# CouchProtato-BOTTOM.net
KiCad netlist of a schematic drawn in EAGLE
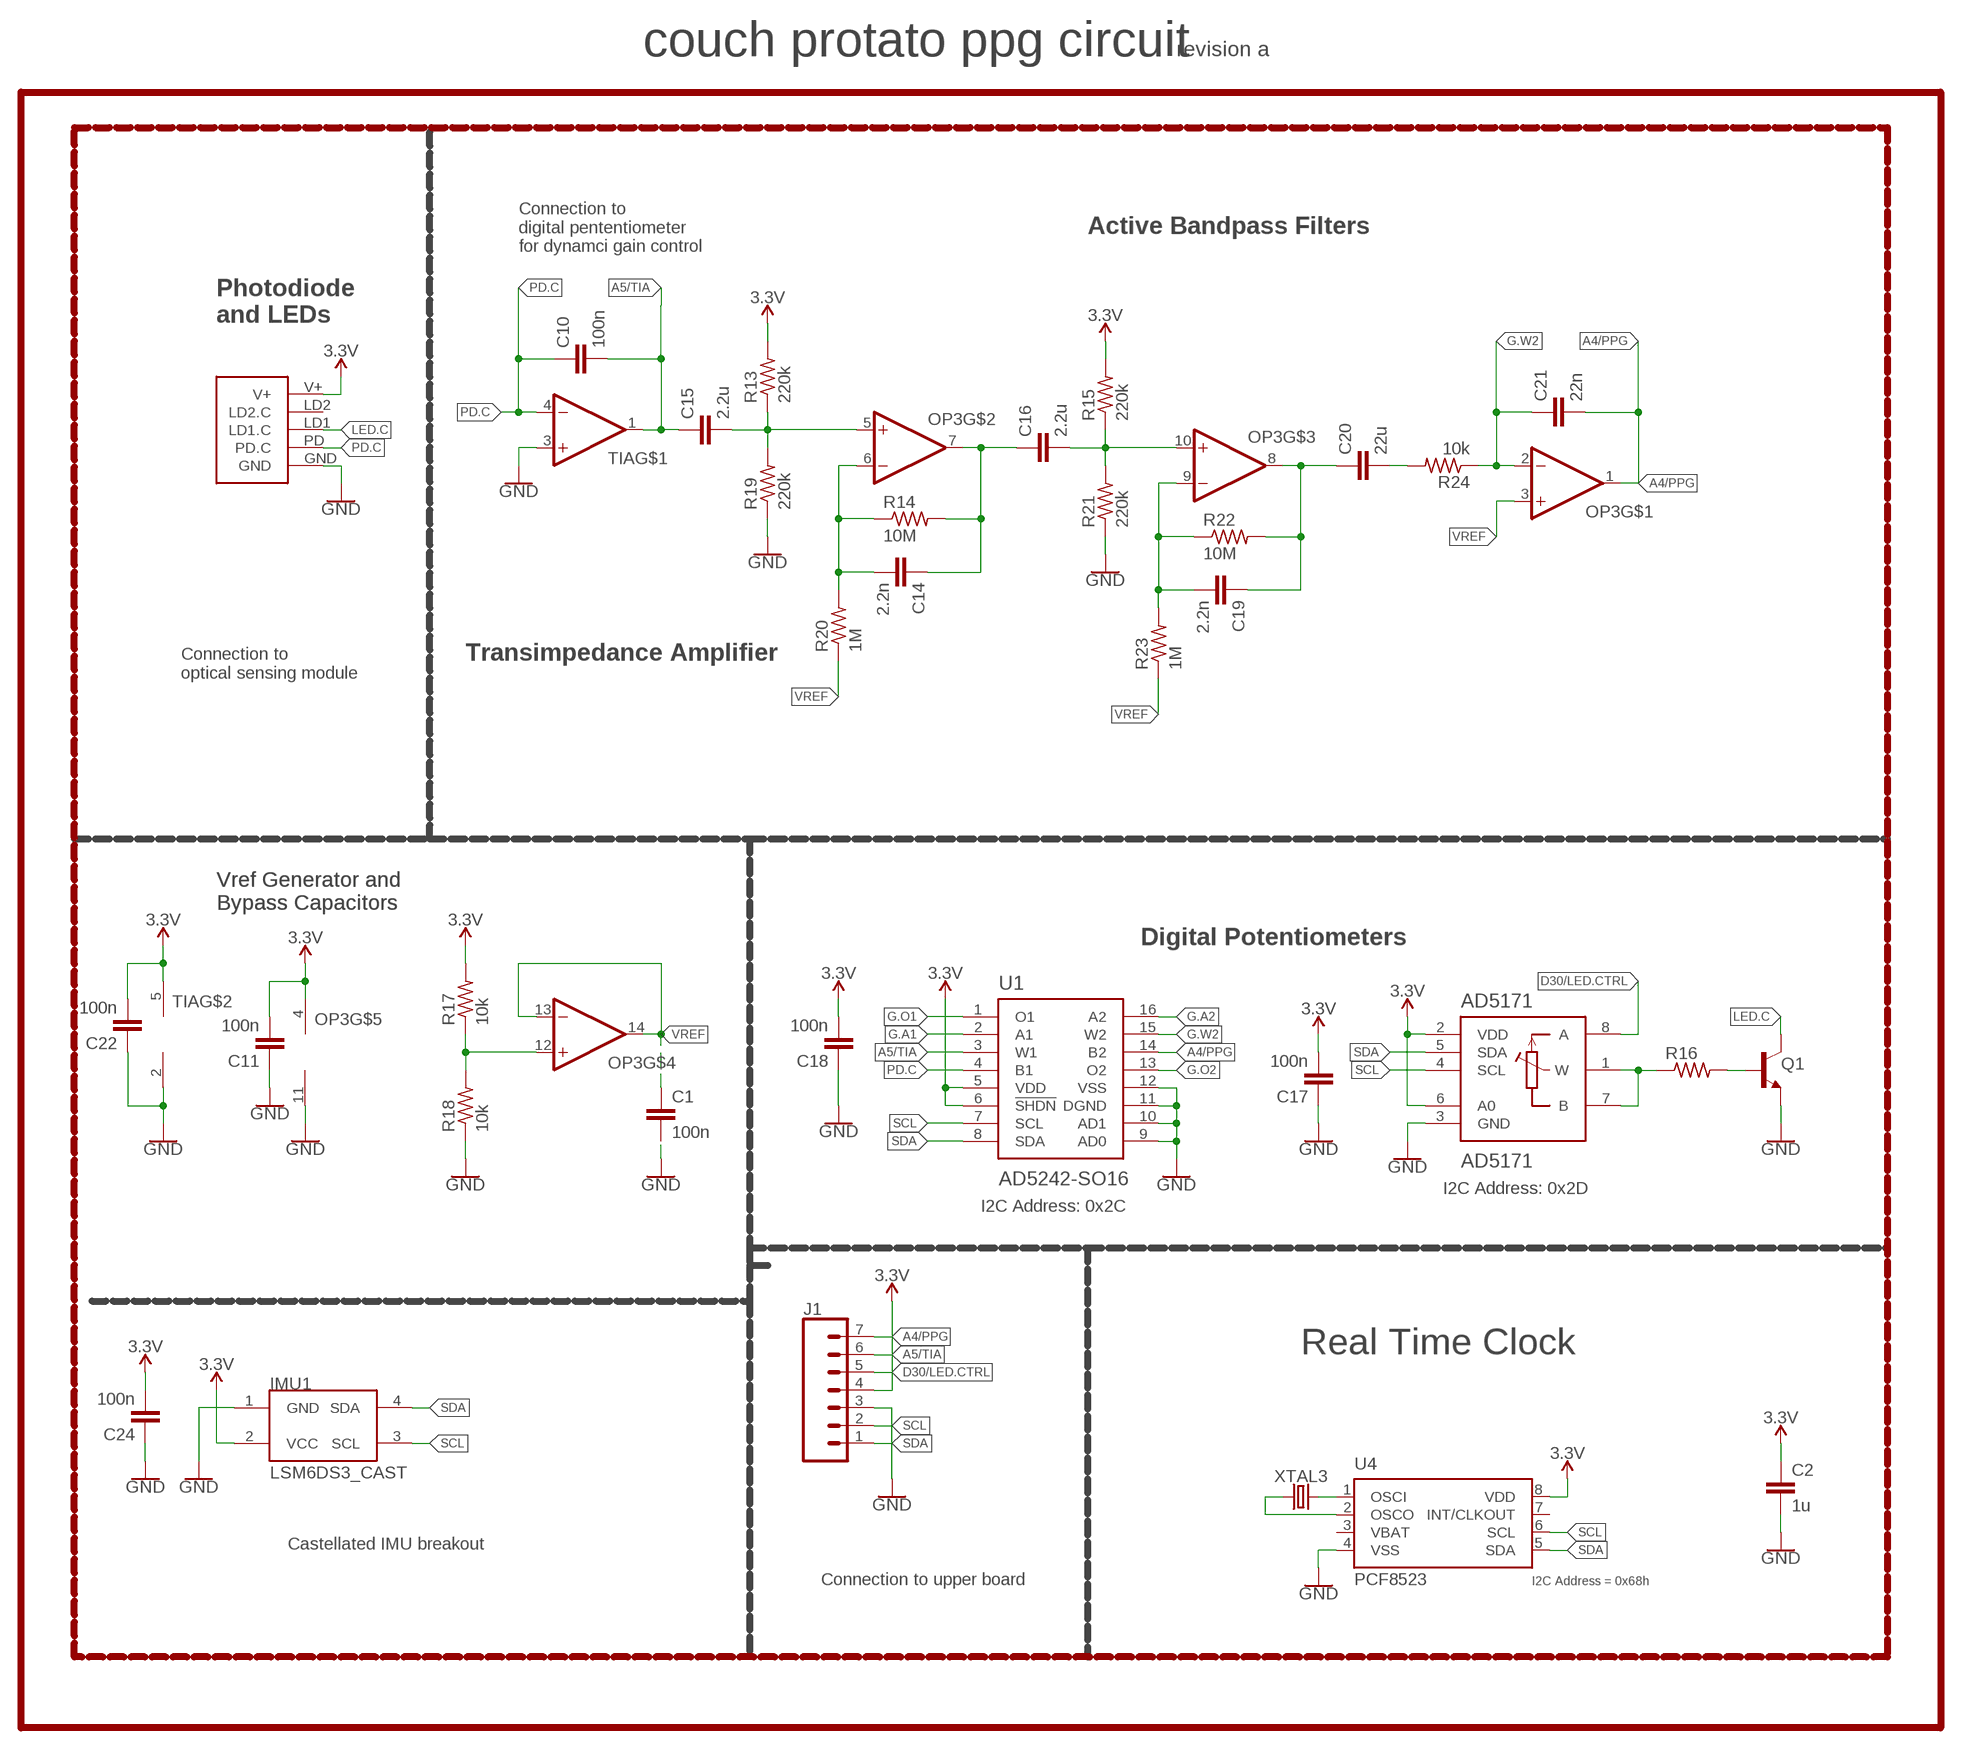
[diagram p0: schematic, sheet 1]

(export (version "E")
  (design (tool "Eeschema 10.0.6"))
  (components
    (comp (ref "AD5171")
      (value "AD5171")
      (footprint "eagle-import:SOT-23-8")
      (libsource (lib "eagle-import") (part "AD5171"))
    )
    (comp (ref "C1")
      (value "100n")
      (footprint "eagle-import:C0603")
      (libsource (lib "eagle-import") (part "CAPACITOR0603"))
    )
    (comp (ref "C2")
      (value "1u")
      (footprint "eagle-import:C0603")
      (libsource (lib "eagle-import") (part "CAPACITOR0603"))
    )
    (comp (ref "C10")
      (value "100n")
      (footprint "eagle-import:C0603")
      (libsource (lib "eagle-import") (part "CAPACITOR0603"))
    )
    (comp (ref "C11")
      (value "100n")
      (footprint "eagle-import:C0603")
      (libsource (lib "eagle-import") (part "CAPACITOR0603"))
    )
    (comp (ref "C14")
      (value "2.2n")
      (footprint "eagle-import:C0603")
      (libsource (lib "eagle-import") (part "CAPACITOR0603"))
    )
    (comp (ref "C15")
      (value "2.2u")
      (footprint "eagle-import:C0603")
      (libsource (lib "eagle-import") (part "CAPACITOR0603"))
    )
    (comp (ref "C16")
      (value "2.2u")
      (footprint "eagle-import:C0603")
      (libsource (lib "eagle-import") (part "CAPACITOR0603"))
    )
    (comp (ref "C17")
      (value "100n")
      (footprint "eagle-import:C0603")
      (libsource (lib "eagle-import") (part "CAPACITOR0603"))
    )
    (comp (ref "C18")
      (value "100n")
      (footprint "eagle-import:C0603")
      (libsource (lib "eagle-import") (part "CAPACITOR0603"))
    )
    (comp (ref "C19")
      (value "2.2n")
      (footprint "eagle-import:C0603")
      (libsource (lib "eagle-import") (part "CAPACITOR0603"))
    )
    (comp (ref "C20")
      (value "22u")
      (footprint "eagle-import:C0603")
      (libsource (lib "eagle-import") (part "CAPACITOR0603"))
    )
    (comp (ref "C21")
      (value "22n")
      (footprint "eagle-import:C0603")
      (libsource (lib "eagle-import") (part "CAPACITOR0603"))
    )
    (comp (ref "C22")
      (value "100n")
      (footprint "eagle-import:C0603")
      (libsource (lib "eagle-import") (part "CAPACITOR0603"))
    )
    (comp (ref "C24")
      (value "100n")
      (footprint "eagle-import:C0603")
      (libsource (lib "eagle-import") (part "CAPACITOR0603"))
    )
    (comp (ref "IMU1")
      (value "LSM6DS3_CAST")
      (footprint "eagle-import:LSM6DS3_CAST")
      (libsource (lib "eagle-import") (part "LSM6DS3_CAST"))
    )
    (comp (ref "J1")
      (value "CONN_07-1.27MM")
      (footprint "eagle-import:1X07_1.27MM")
      (libsource (lib "eagle-import") (part "CONN_07-1.27MM"))
    )
    (comp (ref "OP3")
      (value "OP-QUAD-SO14")
      (footprint "eagle-import:SO14")
      (libsource (lib "eagle-import") (part "OP-QUAD-SO14"))
    )
    (comp (ref "Q1")
      (value "NPN-GENERIC")
      (footprint "eagle-import:SOT23-3")
      (libsource (lib "eagle-import") (part "NPN-GENERIC"))
    )
    (comp (ref "R13")
      (value "220k")
      (footprint "eagle-import:R0603")
      (libsource (lib "eagle-import") (part "RESISTOR0603"))
    )
    (comp (ref "R14")
      (value "10M")
      (footprint "eagle-import:R0603")
      (libsource (lib "eagle-import") (part "RESISTOR0603"))
    )
    (comp (ref "R15")
      (value "220k")
      (footprint "eagle-import:R0603")
      (libsource (lib "eagle-import") (part "RESISTOR0603"))
    )
    (comp (ref "R16")
      (value "RESISTOR0603")
      (footprint "eagle-import:R0603")
      (libsource (lib "eagle-import") (part "RESISTOR0603"))
    )
    (comp (ref "R17")
      (value "10k")
      (footprint "eagle-import:R0402")
      (libsource (lib "eagle-import") (part "RESISTOR0402"))
    )
    (comp (ref "R18")
      (value "10k")
      (footprint "eagle-import:R0402")
      (libsource (lib "eagle-import") (part "RESISTOR0402"))
    )
    (comp (ref "R19")
      (value "220k")
      (footprint "eagle-import:R0603")
      (libsource (lib "eagle-import") (part "RESISTOR0603"))
    )
    (comp (ref "R20")
      (value "1M")
      (footprint "eagle-import:R0603")
      (libsource (lib "eagle-import") (part "RESISTOR0603"))
    )
    (comp (ref "R21")
      (value "220k")
      (footprint "eagle-import:R0603")
      (libsource (lib "eagle-import") (part "RESISTOR0603"))
    )
    (comp (ref "R22")
      (value "10M")
      (footprint "eagle-import:R0603")
      (libsource (lib "eagle-import") (part "RESISTOR0603"))
    )
    (comp (ref "R23")
      (value "1M")
      (footprint "eagle-import:R0603")
      (libsource (lib "eagle-import") (part "RESISTOR0603"))
    )
    (comp (ref "R24")
      (value "10k")
      (footprint "eagle-import:R0603")
      (libsource (lib "eagle-import") (part "RESISTOR0603"))
    )
    (comp (ref "TIA")
      (value "OP-SINGLEOT")
      (footprint "eagle-import:SOT23-5")
      (libsource (lib "eagle-import") (part "OP-SINGLEOT"))
    )
    (comp (ref "U$3")
      (value "PPG.MODULE.2")
      (footprint "eagle-import:PPG.MODULE.2")
      (libsource (lib "eagle-import") (part "PPG.MODULE.2"))
    )
    (comp (ref "U1")
      (value "AD5242-SO16")
      (footprint "eagle-import:SO16")
      (libsource (lib "eagle-import") (part "AD5242-SO16"))
    )
    (comp (ref "U4")
      (value "PCF8523")
      (footprint "eagle-import:SO8")
      (libsource (lib "eagle-import") (part "PCF8523"))
    )
    (comp (ref "XTAL3")
      (value "32.7680kHz")
      (footprint "eagle-import:2-SMD.NOLEAD.2.0MMTO1.2MM")
      (fields (field (name "FREQ") "32.7680KHZ"))
      (libsource (lib "eagle-import") (part "CRYSTALECS-.327-12.5-12-C-TR"))
    )
  )
  (nets
    (net (code "1") (name "/VBAT") (class "Default")
      (node (ref "U4") (pin "3") (pinfunction "VBAT_3") (pintype "power_in"))
    )
    (net (code "2") (name "3.3V") (class "Default")
      (node (ref "AD5171") (pin "2") (pinfunction "VDD_2") (pintype "bidirectional"))
      (node (ref "AD5171") (pin "6") (pinfunction "A0_6") (pintype "bidirectional"))
      (node (ref "C11") (pin "2") (pinfunction "2_2") (pintype "passive"))
      (node (ref "C17") (pin "2") (pinfunction "2_2") (pintype "passive"))
      (node (ref "C18") (pin "2") (pinfunction "2_2") (pintype "passive"))
      (node (ref "C2") (pin "1") (pinfunction "1_1") (pintype "passive"))
      (node (ref "C22") (pin "2") (pinfunction "2_2") (pintype "passive"))
      (node (ref "C24") (pin "2") (pinfunction "2_2") (pintype "passive"))
      (node (ref "IMU1") (pin "2") (pinfunction "VCC_2") (pintype "bidirectional"))
      (node (ref "J1") (pin "4") (pinfunction "4_4") (pintype "passive"))
      (node (ref "OP3") (pin "4") (pinfunction "V+_4") (pintype "power_in"))
      (node (ref "R13") (pin "2") (pinfunction "2_2") (pintype "passive"))
      (node (ref "R15") (pin "2") (pinfunction "2_2") (pintype "passive"))
      (node (ref "R17") (pin "2") (pinfunction "2_2") (pintype "passive"))
      (node (ref "TIA") (pin "5") (pinfunction "V+_5") (pintype "power_in"))
      (node (ref "U$3") (pin "V+") (pinfunction "V+_V+") (pintype "bidirectional"))
      (node (ref "U1") (pin "5") (pinfunction "VDD_5") (pintype "bidirectional"))
      (node (ref "U1") (pin "6") (pinfunction "~{SHDN}_6") (pintype "bidirectional"))
      (node (ref "U4") (pin "8") (pinfunction "VDD_8") (pintype "power_in"))
    )
    (net (code "3") (name "A4{slash}PPG") (class "Default")
      (node (ref "C21") (pin "2") (pinfunction "2_2") (pintype "passive"))
      (node (ref "J1") (pin "7") (pinfunction "7_7") (pintype "passive"))
      (node (ref "OP3") (pin "1") (pinfunction "OUT_1") (pintype "output"))
      (node (ref "U1") (pin "14") (pinfunction "B2_14") (pintype "bidirectional"))
    )
    (net (code "4") (name "A5{slash}TIA") (class "Default")
      (node (ref "C10") (pin "2") (pinfunction "2_2") (pintype "passive"))
      (node (ref "C15") (pin "1") (pinfunction "1_1") (pintype "passive"))
      (node (ref "J1") (pin "6") (pinfunction "6_6") (pintype "passive"))
      (node (ref "TIA") (pin "1") (pinfunction "OUT_1") (pintype "output"))
      (node (ref "U1") (pin "3") (pinfunction "W1_3") (pintype "bidirectional"))
    )
    (net (code "5") (name "D30{slash}LED.CTRL") (class "Default")
      (node (ref "AD5171") (pin "8") (pinfunction "A_8") (pintype "bidirectional"))
      (node (ref "J1") (pin "5") (pinfunction "5_5") (pintype "passive"))
    )
    (net (code "6") (name "G.A1") (class "Default")
      (node (ref "U1") (pin "2") (pinfunction "A1_2") (pintype "bidirectional"))
    )
    (net (code "7") (name "G.A2") (class "Default")
      (node (ref "U1") (pin "16") (pinfunction "A2_16") (pintype "bidirectional"))
    )
    (net (code "8") (name "G.O1") (class "Default")
      (node (ref "U1") (pin "1") (pinfunction "O1_1") (pintype "bidirectional"))
    )
    (net (code "9") (name "G.O2") (class "Default")
      (node (ref "U1") (pin "13") (pinfunction "O2_13") (pintype "bidirectional"))
    )
    (net (code "10") (name "G.W2") (class "Default")
      (node (ref "C21") (pin "1") (pinfunction "1_1") (pintype "passive"))
      (node (ref "OP3") (pin "2") (pinfunction "-IN_2") (pintype "input"))
      (node (ref "R24") (pin "1") (pinfunction "1_1") (pintype "passive"))
      (node (ref "U1") (pin "15") (pinfunction "W2_15") (pintype "bidirectional"))
    )
    (net (code "11") (name "GND") (class "Default")
      (node (ref "AD5171") (pin "3") (pinfunction "GND_3") (pintype "bidirectional"))
      (node (ref "C1") (pin "2") (pinfunction "2_2") (pintype "passive"))
      (node (ref "C11") (pin "1") (pinfunction "1_1") (pintype "passive"))
      (node (ref "C17") (pin "1") (pinfunction "1_1") (pintype "passive"))
      (node (ref "C18") (pin "1") (pinfunction "1_1") (pintype "passive"))
      (node (ref "C2") (pin "2") (pinfunction "2_2") (pintype "passive"))
      (node (ref "C22") (pin "1") (pinfunction "1_1") (pintype "passive"))
      (node (ref "C24") (pin "1") (pinfunction "1_1") (pintype "passive"))
      (node (ref "IMU1") (pin "1") (pinfunction "GND_1") (pintype "bidirectional"))
      (node (ref "J1") (pin "3") (pinfunction "3_3") (pintype "passive"))
      (node (ref "OP3") (pin "11") (pinfunction "V-_11") (pintype "power_in"))
      (node (ref "Q1") (pin "2") (pinfunction "E_2") (pintype "passive"))
      (node (ref "R18") (pin "1") (pinfunction "1_1") (pintype "passive"))
      (node (ref "R19") (pin "1") (pinfunction "1_1") (pintype "passive"))
      (node (ref "R21") (pin "1") (pinfunction "1_1") (pintype "passive"))
      (node (ref "TIA") (pin "2") (pinfunction "V-_2") (pintype "power_in"))
      (node (ref "TIA") (pin "3") (pinfunction "+IN_3") (pintype "input"))
      (node (ref "U$3") (pin "GND") (pinfunction "GND_GND") (pintype "bidirectional"))
      (node (ref "U1") (pin "10") (pinfunction "AD1_10") (pintype "bidirectional"))
      (node (ref "U1") (pin "11") (pinfunction "DGND_11") (pintype "bidirectional"))
      (node (ref "U1") (pin "12") (pinfunction "VSS_12") (pintype "bidirectional"))
      (node (ref "U1") (pin "9") (pinfunction "AD0_9") (pintype "bidirectional"))
      (node (ref "U4") (pin "4") (pinfunction "VSS_4") (pintype "power_in"))
    )
    (net (code "12") (name "LED.C") (class "Default")
      (node (ref "Q1") (pin "3") (pinfunction "C_3") (pintype "passive"))
      (node (ref "U$3") (pin "LD1") (pinfunction "LD1.C_LD1") (pintype "bidirectional"))
    )
    (net (code "13") (name "Net-(AD5171-B)") (class "Default")
      (node (ref "AD5171") (pin "1") (pinfunction "W_1") (pintype "bidirectional"))
      (node (ref "AD5171") (pin "7") (pinfunction "B_7") (pintype "bidirectional"))
      (node (ref "R16") (pin "1") (pinfunction "1_1") (pintype "passive"))
    )
    (net (code "14") (name "Net-(C20-Pad2)") (class "Default")
      (node (ref "C20") (pin "2") (pinfunction "2_2") (pintype "passive"))
      (node (ref "R24") (pin "2") (pinfunction "2_2") (pintype "passive"))
    )
    (net (code "15") (name "Net-(OP3B-+IN)") (class "Default")
      (node (ref "C15") (pin "2") (pinfunction "2_2") (pintype "passive"))
      (node (ref "OP3") (pin "5") (pinfunction "+IN_5") (pintype "input"))
      (node (ref "R13") (pin "1") (pinfunction "1_1") (pintype "passive"))
      (node (ref "R19") (pin "2") (pinfunction "2_2") (pintype "passive"))
    )
    (net (code "16") (name "Net-(OP3B--IN)") (class "Default")
      (node (ref "C14") (pin "2") (pinfunction "2_2") (pintype "passive"))
      (node (ref "OP3") (pin "6") (pinfunction "-IN_6") (pintype "input"))
      (node (ref "R14") (pin "1") (pinfunction "1_1") (pintype "passive"))
      (node (ref "R20") (pin "2") (pinfunction "2_2") (pintype "passive"))
    )
    (net (code "17") (name "Net-(OP3B-OUT)") (class "Default")
      (node (ref "C14") (pin "1") (pinfunction "1_1") (pintype "passive"))
      (node (ref "C16") (pin "1") (pinfunction "1_1") (pintype "passive"))
      (node (ref "OP3") (pin "7") (pinfunction "OUT_7") (pintype "output"))
      (node (ref "R14") (pin "2") (pinfunction "2_2") (pintype "passive"))
    )
    (net (code "18") (name "Net-(OP3C-+IN)") (class "Default")
      (node (ref "C16") (pin "2") (pinfunction "2_2") (pintype "passive"))
      (node (ref "OP3") (pin "10") (pinfunction "+IN_10") (pintype "input"))
      (node (ref "R15") (pin "1") (pinfunction "1_1") (pintype "passive"))
      (node (ref "R21") (pin "2") (pinfunction "2_2") (pintype "passive"))
    )
    (net (code "19") (name "Net-(OP3C--IN)") (class "Default")
      (node (ref "C19") (pin "2") (pinfunction "2_2") (pintype "passive"))
      (node (ref "OP3") (pin "9") (pinfunction "-IN_9") (pintype "input"))
      (node (ref "R22") (pin "1") (pinfunction "1_1") (pintype "passive"))
      (node (ref "R23") (pin "2") (pinfunction "2_2") (pintype "passive"))
    )
    (net (code "20") (name "Net-(OP3C-OUT)") (class "Default")
      (node (ref "C19") (pin "1") (pinfunction "1_1") (pintype "passive"))
      (node (ref "C20") (pin "1") (pinfunction "1_1") (pintype "passive"))
      (node (ref "OP3") (pin "8") (pinfunction "OUT_8") (pintype "output"))
      (node (ref "R22") (pin "2") (pinfunction "2_2") (pintype "passive"))
    )
    (net (code "21") (name "Net-(OP3D-+IN)") (class "Default")
      (node (ref "OP3") (pin "12") (pinfunction "+IN_12") (pintype "input"))
      (node (ref "R17") (pin "1") (pinfunction "1_1") (pintype "passive"))
      (node (ref "R18") (pin "2") (pinfunction "2_2") (pintype "passive"))
    )
    (net (code "22") (name "Net-(Q1-B)") (class "Default")
      (node (ref "Q1") (pin "1") (pinfunction "B_1") (pintype "passive"))
      (node (ref "R16") (pin "2") (pinfunction "2_2") (pintype "passive"))
    )
    (net (code "23") (name "Net-(U4-OSCI)") (class "Default")
      (node (ref "U4") (pin "1") (pinfunction "OSCI_1") (pintype "bidirectional"))
      (node (ref "XTAL3") (pin "P$2") (pinfunction "2_P$2") (pintype "passive"))
    )
    (net (code "24") (name "Net-(U4-OSCO)") (class "Default")
      (node (ref "U4") (pin "2") (pinfunction "OSCO_2") (pintype "bidirectional"))
      (node (ref "XTAL3") (pin "P$1") (pinfunction "1_P$1") (pintype "passive"))
    )
    (net (code "25") (name "PD.C") (class "Default")
      (node (ref "C10") (pin "1") (pinfunction "1_1") (pintype "passive"))
      (node (ref "TIA") (pin "4") (pinfunction "-IN_4") (pintype "input"))
      (node (ref "U$3") (pin "PD") (pinfunction "PD.C_PD") (pintype "bidirectional"))
      (node (ref "U1") (pin "4") (pinfunction "B1_4") (pintype "bidirectional"))
    )
    (net (code "26") (name "SCL") (class "Default")
      (node (ref "AD5171") (pin "4") (pinfunction "SCL_4") (pintype "bidirectional"))
      (node (ref "IMU1") (pin "3") (pinfunction "SCL_3") (pintype "bidirectional"))
      (node (ref "J1") (pin "2") (pinfunction "2_2") (pintype "passive"))
      (node (ref "U1") (pin "7") (pinfunction "SCL_7") (pintype "bidirectional"))
      (node (ref "U4") (pin "6") (pinfunction "SCL_6") (pintype "bidirectional"))
    )
    (net (code "27") (name "SDA") (class "Default")
      (node (ref "AD5171") (pin "5") (pinfunction "SDA_5") (pintype "bidirectional"))
      (node (ref "IMU1") (pin "4") (pinfunction "SDA_4") (pintype "bidirectional"))
      (node (ref "J1") (pin "1") (pinfunction "1_1") (pintype "passive"))
      (node (ref "U1") (pin "8") (pinfunction "SDA_8") (pintype "bidirectional"))
      (node (ref "U4") (pin "5") (pinfunction "SDA_5") (pintype "bidirectional"))
    )
    (net (code "28") (name "VREF") (class "Default")
      (node (ref "C1") (pin "1") (pinfunction "1_1") (pintype "passive"))
      (node (ref "OP3") (pin "13") (pinfunction "-IN_13") (pintype "input"))
      (node (ref "OP3") (pin "14") (pinfunction "OUT_14") (pintype "output"))
      (node (ref "OP3") (pin "3") (pinfunction "+IN_3") (pintype "input"))
      (node (ref "R20") (pin "1") (pinfunction "1_1") (pintype "passive"))
      (node (ref "R23") (pin "1") (pinfunction "1_1") (pintype "passive"))
    )
    (net (code "29") (name "unconnected-(U$3-LD2.C-PadLD2)") (class "Default")
      (node (ref "U$3") (pin "LD2") (pinfunction "LD2.C_LD2") (pintype "bidirectional"))
    )
    (net (code "30") (name "unconnected-(U4-INT{slash}CLKOUT-Pad7)") (class "Default")
      (node (ref "U4") (pin "7") (pinfunction "INT/CLKOUT_7") (pintype "bidirectional"))
    )
  )
)
